# WBDR_02.net
KiCad netlist of a schematic drawn in EAGLE
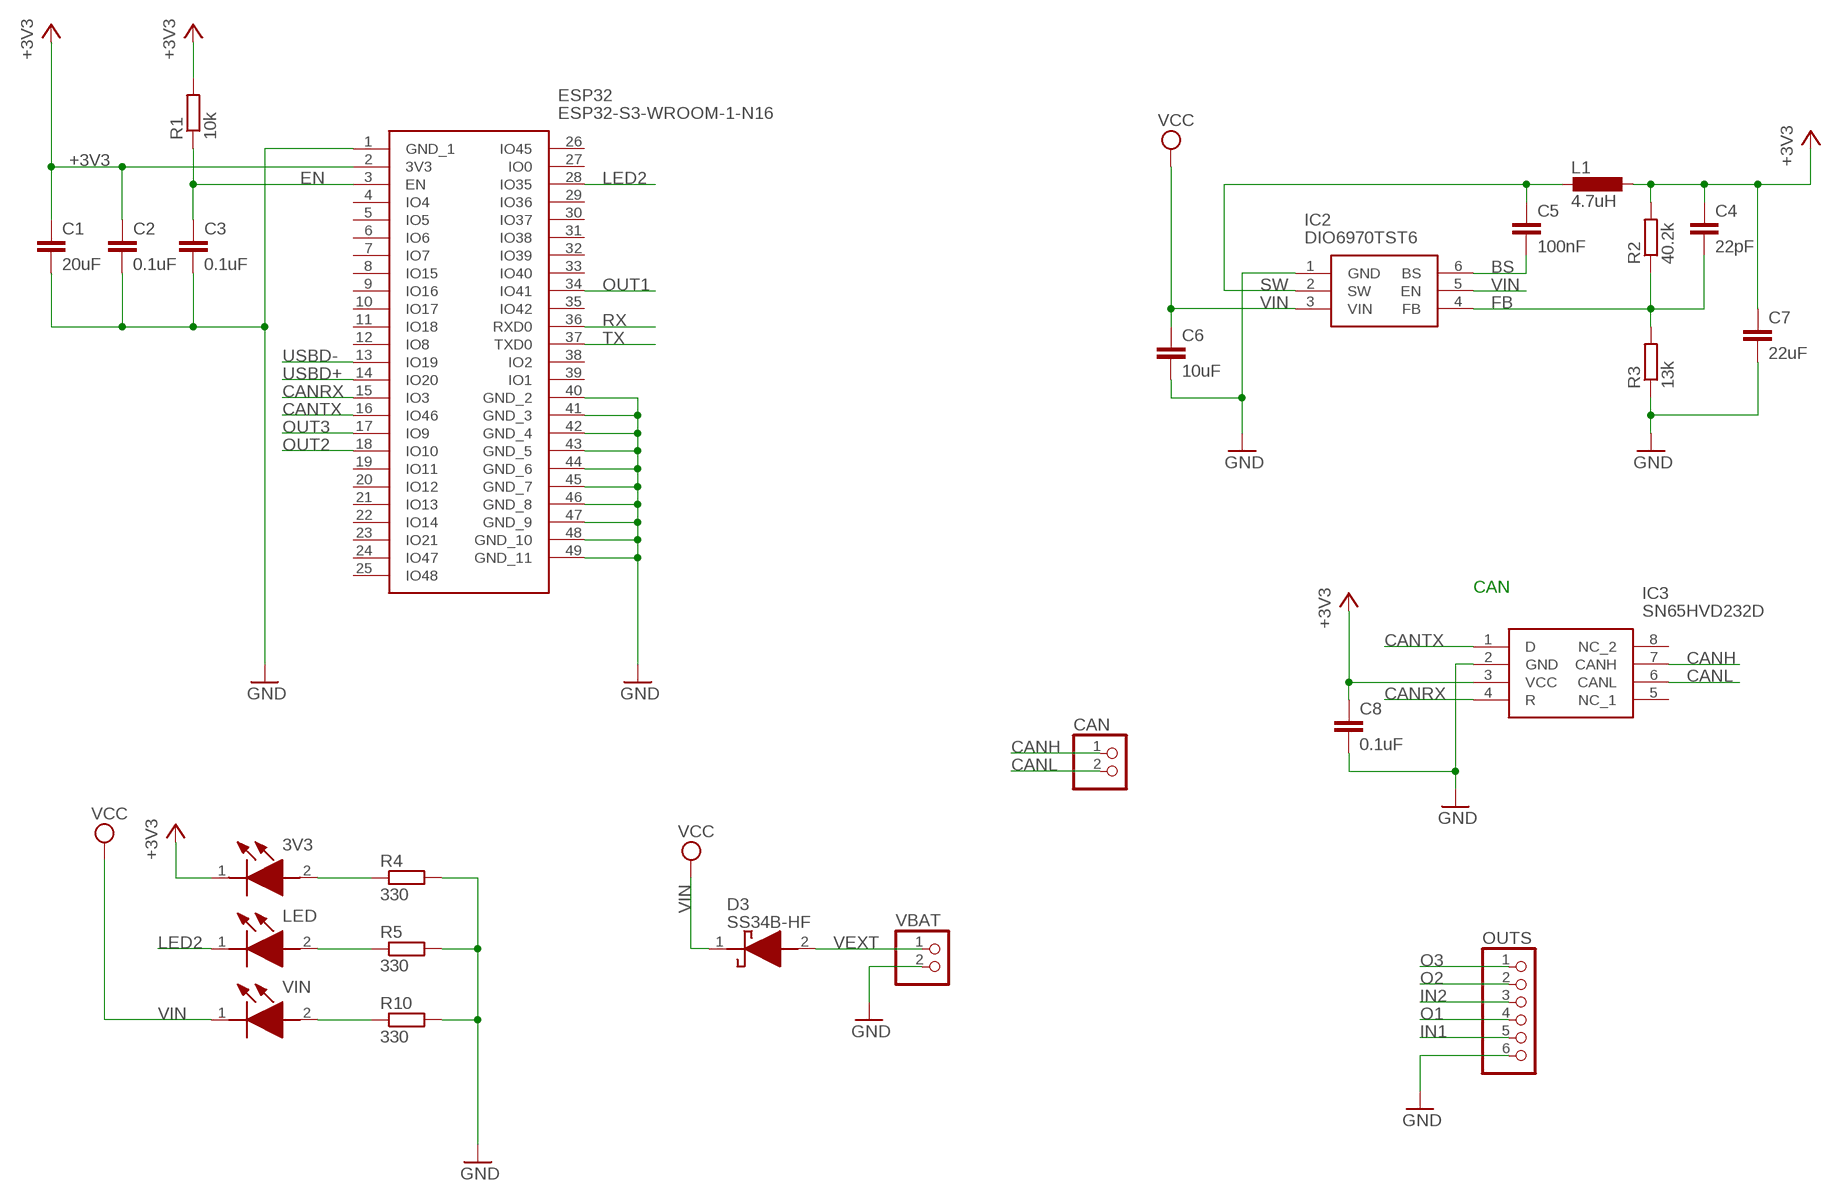
[diagram p0: schematic, sheet 1, part 1 of 2]
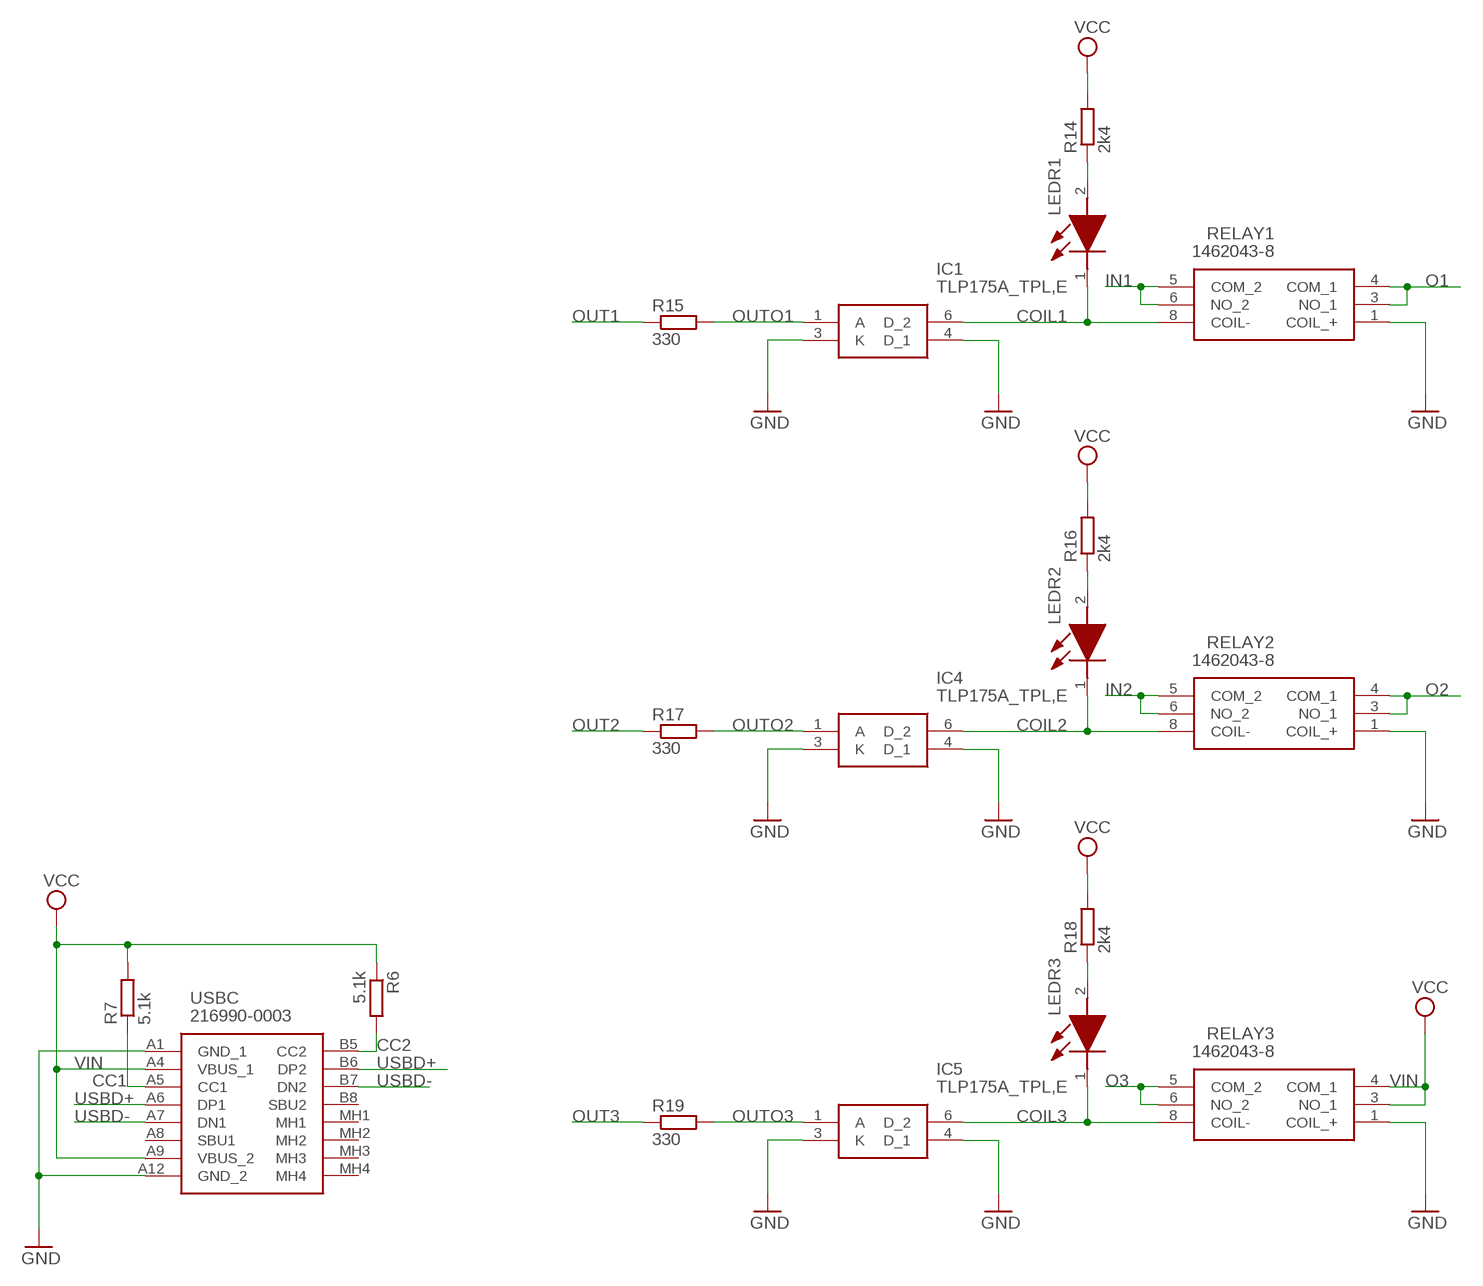
[diagram p1: schematic, sheet 1, part 2 of 2]

(export (version "E")
  (design (tool "Eeschema 10.0.6"))
  (components
    (comp (ref "3V3")
      (value "150060GS75000")
      (footprint "eagle-import:LEDC1608X80N")
      (fields (field (name "MOUSER_PART_NUMBER") "710-150060GS75000"))
      (libsource (lib "eagle-import") (part "150060GS75000"))
    )
    (comp (ref "C1")
      (value "20uF")
      (footprint "eagle-import:C0603")
      (libsource (lib "eagle-import") (part "C-EUC0603"))
    )
    (comp (ref "C2")
      (value "0.1uF")
      (footprint "eagle-import:C0603")
      (libsource (lib "eagle-import") (part "C-EUC0603"))
    )
    (comp (ref "C3")
      (value "0.1uF")
      (footprint "eagle-import:C0603")
      (libsource (lib "eagle-import") (part "C-EUC0603"))
    )
    (comp (ref "C4")
      (value "22pF")
      (footprint "eagle-import:C0603")
      (libsource (lib "eagle-import") (part "C-EUC0603"))
    )
    (comp (ref "C5")
      (value "100nF")
      (footprint "eagle-import:C0603")
      (libsource (lib "eagle-import") (part "C-EUC0603"))
    )
    (comp (ref "C6")
      (value "10uF")
      (footprint "eagle-import:C0603")
      (libsource (lib "eagle-import") (part "C-EUC0603"))
    )
    (comp (ref "C7")
      (value "22uF")
      (footprint "eagle-import:C0603")
      (libsource (lib "eagle-import") (part "C-EUC0603"))
    )
    (comp (ref "C8")
      (value "0.1uF")
      (footprint "eagle-import:C0603")
      (libsource (lib "eagle-import") (part "C-EUC0603"))
    )
    (comp (ref "CAN")
      (value "PINHD-1X2")
      (footprint "eagle-import:1X02")
      (libsource (lib "eagle-import") (part "PINHD-1X2"))
    )
    (comp (ref "D3")
      (value "SS34B-HF")
      (footprint "eagle-import:DIOM5336X320N")
      (fields (field (name "MOUSER_PART_NUMBER") "750-SS34B-HF"))
      (libsource (lib "eagle-import") (part "SS34B-HF"))
    )
    (comp (ref "ESP32")
      (value "ESP32-S3-WROOM-1-N16")
      (footprint "eagle-import:ESP32S3WROOM1N16")
      (fields (field (name "MOUSER_PART_NUMBER") "356-ESP32S3WROOM1N16"))
      (libsource (lib "eagle-import") (part "ESP32-S3-WROOM-1-N16"))
    )
    (comp (ref "IC1")
      (value "TLP175A_TPL,E")
      (footprint "eagle-import:TLP266J")
      (fields
        (field (name "MANUFACTURER_PART_NUMBER") "TLP175A(TPL,E")
        (field (name "MOUSER_PART_NUMBER") "757-TLP175A(TPLE")
      )
      (libsource (lib "eagle-import") (part "TLP175A_TPL,E"))
    )
    (comp (ref "IC2")
      (value "DIO6970TST6")
      (footprint "eagle-import:SOT95P280X90-6N")
      (fields (field (name "MOUSER_PART_NUMBER") "453-DIO6970ST6"))
      (libsource (lib "eagle-import") (part "DIO6970TST6"))
    )
    (comp (ref "IC3")
      (value "SN65HVD232D")
      (footprint "eagle-import:SOIC127P600X175-8N")
      (fields (field (name "MOUSER_PART_NUMBER") "595-SN65HVD232D"))
      (libsource (lib "eagle-import") (part "SN65HVD232D"))
    )
    (comp (ref "IC4")
      (value "TLP175A_TPL,E")
      (footprint "eagle-import:TLP266J")
      (fields
        (field (name "MANUFACTURER_PART_NUMBER") "TLP175A(TPL,E")
        (field (name "MOUSER_PART_NUMBER") "757-TLP175A(TPLE")
      )
      (libsource (lib "eagle-import") (part "TLP175A_TPL,E"))
    )
    (comp (ref "IC5")
      (value "TLP175A_TPL,E")
      (footprint "eagle-import:TLP266J")
      (fields
        (field (name "MANUFACTURER_PART_NUMBER") "TLP175A(TPL,E")
        (field (name "MOUSER_PART_NUMBER") "757-TLP175A(TPLE")
      )
      (libsource (lib "eagle-import") (part "TLP175A_TPL,E"))
    )
    (comp (ref "L1")
      (value "4.7uH")
      (footprint "eagle-import:L5650M")
      (libsource (lib "eagle-import") (part "L-EUL5650M"))
    )
    (comp (ref "LED")
      (value "150060GS75000")
      (footprint "eagle-import:LEDC1608X80N")
      (fields (field (name "MOUSER_PART_NUMBER") "710-150060GS75000"))
      (libsource (lib "eagle-import") (part "150060GS75000"))
    )
    (comp (ref "LEDR1")
      (value "150060GS75000")
      (footprint "eagle-import:LEDC1608X80N")
      (fields (field (name "MOUSER_PART_NUMBER") "710-150060GS75000"))
      (libsource (lib "eagle-import") (part "150060GS75000"))
    )
    (comp (ref "LEDR2")
      (value "150060GS75000")
      (footprint "eagle-import:LEDC1608X80N")
      (fields (field (name "MOUSER_PART_NUMBER") "710-150060GS75000"))
      (libsource (lib "eagle-import") (part "150060GS75000"))
    )
    (comp (ref "LEDR3")
      (value "150060GS75000")
      (footprint "eagle-import:LEDC1608X80N")
      (fields (field (name "MOUSER_PART_NUMBER") "710-150060GS75000"))
      (libsource (lib "eagle-import") (part "150060GS75000"))
    )
    (comp (ref "OUTS")
      (value "PINHD-1X6")
      (footprint "eagle-import:1X06")
      (libsource (lib "eagle-import") (part "PINHD-1X6"))
    )
    (comp (ref "R1")
      (value "10k")
      (footprint "eagle-import:R0603")
      (libsource (lib "eagle-import") (part "R-EU_R0603"))
    )
    (comp (ref "R2")
      (value "40.2k")
      (footprint "eagle-import:R0603")
      (libsource (lib "eagle-import") (part "R-EU_R0603"))
    )
    (comp (ref "R3")
      (value "13k")
      (footprint "eagle-import:R0603")
      (libsource (lib "eagle-import") (part "R-EU_R0603"))
    )
    (comp (ref "R4")
      (value "330")
      (footprint "eagle-import:R0603")
      (libsource (lib "eagle-import") (part "R-EU_R0603"))
    )
    (comp (ref "R5")
      (value "330")
      (footprint "eagle-import:R0603")
      (libsource (lib "eagle-import") (part "R-EU_R0603"))
    )
    (comp (ref "R6")
      (value "5.1k")
      (footprint "eagle-import:R0603")
      (libsource (lib "eagle-import") (part "R-EU_R0603"))
    )
    (comp (ref "R7")
      (value "5.1k")
      (footprint "eagle-import:R0603")
      (libsource (lib "eagle-import") (part "R-EU_R0603"))
    )
    (comp (ref "R10")
      (value "330")
      (footprint "eagle-import:R0603")
      (libsource (lib "eagle-import") (part "R-EU_R0603"))
    )
    (comp (ref "R14")
      (value "2k4")
      (footprint "eagle-import:R0603")
      (libsource (lib "eagle-import") (part "R-EU_R0603"))
    )
    (comp (ref "R15")
      (value "330")
      (footprint "eagle-import:R0603")
      (libsource (lib "eagle-import") (part "R-EU_R0603"))
    )
    (comp (ref "R16")
      (value "2k4")
      (footprint "eagle-import:R0603")
      (libsource (lib "eagle-import") (part "R-EU_R0603"))
    )
    (comp (ref "R17")
      (value "330")
      (footprint "eagle-import:R0603")
      (libsource (lib "eagle-import") (part "R-EU_R0603"))
    )
    (comp (ref "R18")
      (value "2k4")
      (footprint "eagle-import:R0603")
      (libsource (lib "eagle-import") (part "R-EU_R0603"))
    )
    (comp (ref "R19")
      (value "330")
      (footprint "eagle-import:R0603")
      (libsource (lib "eagle-import") (part "R-EU_R0603"))
    )
    (comp (ref "RELAY1")
      (value "1462043-8")
      (footprint "eagle-import:14620438")
      (fields (field (name "MOUSER_PART_NUMBER") "655-1462043-8"))
      (libsource (lib "eagle-import") (part "1462043-8"))
    )
    (comp (ref "RELAY2")
      (value "1462043-8")
      (footprint "eagle-import:14620438")
      (fields (field (name "MOUSER_PART_NUMBER") "655-1462043-8"))
      (libsource (lib "eagle-import") (part "1462043-8"))
    )
    (comp (ref "RELAY3")
      (value "1462043-8")
      (footprint "eagle-import:14620438")
      (fields (field (name "MOUSER_PART_NUMBER") "655-1462043-8"))
      (libsource (lib "eagle-import") (part "1462043-8"))
    )
    (comp (ref "USBC")
      (value "216990-0003")
      (footprint "eagle-import:2169900003")
      (fields (field (name "MOUSER_PART_NUMBER") "538-216990-0003"))
      (libsource (lib "eagle-import") (part "216990-0003"))
    )
    (comp (ref "VBAT")
      (value "PINHD-1X2")
      (footprint "eagle-import:1X02")
      (libsource (lib "eagle-import") (part "PINHD-1X2"))
    )
    (comp (ref "VIN")
      (value "150060GS75000")
      (footprint "eagle-import:LEDC1608X80N")
      (fields (field (name "MOUSER_PART_NUMBER") "710-150060GS75000"))
      (libsource (lib "eagle-import") (part "150060GS75000"))
    )
  )
  (nets
    (net (code "1") (name "+3V3") (class "Default")
      (node (ref "3V3") (pin "1") (pinfunction "K_1") (pintype "bidirectional"))
      (node (ref "C1") (pin "1") (pinfunction "1_1") (pintype "passive"))
      (node (ref "C2") (pin "1") (pinfunction "1_1") (pintype "passive"))
      (node (ref "C4") (pin "1") (pinfunction "1_1") (pintype "passive"))
      (node (ref "C7") (pin "1") (pinfunction "1_1") (pintype "passive"))
      (node (ref "C8") (pin "1") (pinfunction "1_1") (pintype "passive"))
      (node (ref "ESP32") (pin "2") (pinfunction "3V3_2") (pintype "bidirectional"))
      (node (ref "IC3") (pin "3") (pinfunction "VCC_3") (pintype "bidirectional"))
      (node (ref "L1") (pin "1") (pinfunction "1_1") (pintype "passive"))
      (node (ref "R1") (pin "2") (pinfunction "2_2") (pintype "passive"))
      (node (ref "R2") (pin "2") (pinfunction "2_2") (pintype "passive"))
    )
    (net (code "2") (name "/BS") (class "Default")
      (node (ref "C5") (pin "2") (pinfunction "2_2") (pintype "passive"))
      (node (ref "IC2") (pin "6") (pinfunction "BS_6") (pintype "bidirectional"))
    )
    (net (code "3") (name "/CANH") (class "Default")
      (node (ref "CAN") (pin "1") (pinfunction "1_1") (pintype "passive"))
      (node (ref "IC3") (pin "7") (pinfunction "CANH_7") (pintype "bidirectional"))
    )
    (net (code "4") (name "/CANL") (class "Default")
      (node (ref "CAN") (pin "2") (pinfunction "2_2") (pintype "passive"))
      (node (ref "IC3") (pin "6") (pinfunction "CANL_6") (pintype "bidirectional"))
    )
    (net (code "5") (name "/CANRX") (class "Default")
      (node (ref "ESP32") (pin "15") (pinfunction "IO3_15") (pintype "bidirectional"))
      (node (ref "IC3") (pin "4") (pinfunction "R_4") (pintype "bidirectional"))
    )
    (net (code "6") (name "/CANTX") (class "Default")
      (node (ref "ESP32") (pin "16") (pinfunction "IO46_16") (pintype "bidirectional"))
      (node (ref "IC3") (pin "1") (pinfunction "D_1") (pintype "bidirectional"))
    )
    (net (code "7") (name "/CC1") (class "Default")
      (node (ref "R7") (pin "1") (pinfunction "1_1") (pintype "passive"))
      (node (ref "USBC") (pin "A5") (pinfunction "CC1_A5") (pintype "bidirectional"))
    )
    (net (code "8") (name "/CC2") (class "Default")
      (node (ref "R6") (pin "2") (pinfunction "2_2") (pintype "passive"))
      (node (ref "USBC") (pin "B5") (pinfunction "CC2_B5") (pintype "bidirectional"))
    )
    (net (code "9") (name "/COIL1") (class "Default")
      (node (ref "IC1") (pin "6") (pinfunction "D_2_6") (pintype "bidirectional"))
      (node (ref "LEDR1") (pin "1") (pinfunction "K_1") (pintype "bidirectional"))
      (node (ref "RELAY1") (pin "8") (pinfunction "COIL-_8") (pintype "bidirectional"))
    )
    (net (code "10") (name "/COIL2") (class "Default")
      (node (ref "IC4") (pin "6") (pinfunction "D_2_6") (pintype "bidirectional"))
      (node (ref "LEDR2") (pin "1") (pinfunction "K_1") (pintype "bidirectional"))
      (node (ref "RELAY2") (pin "8") (pinfunction "COIL-_8") (pintype "bidirectional"))
    )
    (net (code "11") (name "/COIL3") (class "Default")
      (node (ref "IC5") (pin "6") (pinfunction "D_2_6") (pintype "bidirectional"))
      (node (ref "LEDR3") (pin "1") (pinfunction "K_1") (pintype "bidirectional"))
      (node (ref "RELAY3") (pin "8") (pinfunction "COIL-_8") (pintype "bidirectional"))
    )
    (net (code "12") (name "/EN") (class "Default")
      (node (ref "C3") (pin "1") (pinfunction "1_1") (pintype "passive"))
      (node (ref "ESP32") (pin "3") (pinfunction "EN_3") (pintype "bidirectional"))
      (node (ref "R1") (pin "1") (pinfunction "1_1") (pintype "passive"))
    )
    (net (code "13") (name "/FB") (class "Default")
      (node (ref "C4") (pin "2") (pinfunction "2_2") (pintype "passive"))
      (node (ref "IC2") (pin "4") (pinfunction "FB_4") (pintype "bidirectional"))
      (node (ref "R2") (pin "1") (pinfunction "1_1") (pintype "passive"))
      (node (ref "R3") (pin "2") (pinfunction "2_2") (pintype "passive"))
    )
    (net (code "14") (name "/IN1") (class "Default")
      (node (ref "OUTS") (pin "5") (pinfunction "5_5") (pintype "passive"))
      (node (ref "RELAY1") (pin "5") (pinfunction "COM_2_5") (pintype "bidirectional"))
      (node (ref "RELAY1") (pin "6") (pinfunction "NO_2_6") (pintype "bidirectional"))
    )
    (net (code "15") (name "/IN2") (class "Default")
      (node (ref "OUTS") (pin "3") (pinfunction "3_3") (pintype "passive"))
      (node (ref "RELAY2") (pin "5") (pinfunction "COM_2_5") (pintype "bidirectional"))
      (node (ref "RELAY2") (pin "6") (pinfunction "NO_2_6") (pintype "bidirectional"))
    )
    (net (code "16") (name "/LED2") (class "Default")
      (node (ref "ESP32") (pin "28") (pinfunction "IO35_28") (pintype "bidirectional"))
      (node (ref "LED") (pin "1") (pinfunction "K_1") (pintype "bidirectional"))
    )
    (net (code "17") (name "/O1") (class "Default")
      (node (ref "OUTS") (pin "4") (pinfunction "4_4") (pintype "passive"))
      (node (ref "RELAY1") (pin "3") (pinfunction "NO_1_3") (pintype "bidirectional"))
      (node (ref "RELAY1") (pin "4") (pinfunction "COM_1_4") (pintype "bidirectional"))
    )
    (net (code "18") (name "/O2") (class "Default")
      (node (ref "OUTS") (pin "2") (pinfunction "2_2") (pintype "passive"))
      (node (ref "RELAY2") (pin "3") (pinfunction "NO_1_3") (pintype "bidirectional"))
      (node (ref "RELAY2") (pin "4") (pinfunction "COM_1_4") (pintype "bidirectional"))
    )
    (net (code "19") (name "/O3") (class "Default")
      (node (ref "OUTS") (pin "1") (pinfunction "1_1") (pintype "passive"))
      (node (ref "RELAY3") (pin "5") (pinfunction "COM_2_5") (pintype "bidirectional"))
      (node (ref "RELAY3") (pin "6") (pinfunction "NO_2_6") (pintype "bidirectional"))
    )
    (net (code "20") (name "/OUT1") (class "Default")
      (node (ref "ESP32") (pin "34") (pinfunction "IO41_34") (pintype "bidirectional"))
      (node (ref "R15") (pin "1") (pinfunction "1_1") (pintype "passive"))
    )
    (net (code "21") (name "/OUT2") (class "Default")
      (node (ref "ESP32") (pin "18") (pinfunction "IO10_18") (pintype "bidirectional"))
      (node (ref "R17") (pin "1") (pinfunction "1_1") (pintype "passive"))
    )
    (net (code "22") (name "/OUT3") (class "Default")
      (node (ref "ESP32") (pin "17") (pinfunction "IO9_17") (pintype "bidirectional"))
      (node (ref "R19") (pin "1") (pinfunction "1_1") (pintype "passive"))
    )
    (net (code "23") (name "/OUTO1") (class "Default")
      (node (ref "IC1") (pin "1") (pinfunction "A_1") (pintype "bidirectional"))
      (node (ref "R15") (pin "2") (pinfunction "2_2") (pintype "passive"))
    )
    (net (code "24") (name "/OUTO2") (class "Default")
      (node (ref "IC4") (pin "1") (pinfunction "A_1") (pintype "bidirectional"))
      (node (ref "R17") (pin "2") (pinfunction "2_2") (pintype "passive"))
    )
    (net (code "25") (name "/OUTO3") (class "Default")
      (node (ref "IC5") (pin "1") (pinfunction "A_1") (pintype "bidirectional"))
      (node (ref "R19") (pin "2") (pinfunction "2_2") (pintype "passive"))
    )
    (net (code "26") (name "/RX") (class "Default")
      (node (ref "ESP32") (pin "36") (pinfunction "RXD0_36") (pintype "bidirectional"))
    )
    (net (code "27") (name "/SW") (class "Default")
      (node (ref "C5") (pin "1") (pinfunction "1_1") (pintype "passive"))
      (node (ref "IC2") (pin "2") (pinfunction "SW_2") (pintype "bidirectional"))
      (node (ref "L1") (pin "2") (pinfunction "2_2") (pintype "passive"))
    )
    (net (code "28") (name "/TX") (class "Default")
      (node (ref "ESP32") (pin "37") (pinfunction "TXD0_37") (pintype "bidirectional"))
    )
    (net (code "29") (name "/USBD+") (class "Default")
      (node (ref "ESP32") (pin "14") (pinfunction "IO20_14") (pintype "bidirectional"))
      (node (ref "USBC") (pin "A6") (pinfunction "DP1_A6") (pintype "bidirectional"))
      (node (ref "USBC") (pin "B6") (pinfunction "DP2_B6") (pintype "bidirectional"))
    )
    (net (code "30") (name "/USBD-") (class "Default")
      (node (ref "ESP32") (pin "13") (pinfunction "IO19_13") (pintype "bidirectional"))
      (node (ref "USBC") (pin "A7") (pinfunction "DN1_A7") (pintype "bidirectional"))
      (node (ref "USBC") (pin "B7") (pinfunction "DN2_B7") (pintype "bidirectional"))
    )
    (net (code "31") (name "/VEXT") (class "Default")
      (node (ref "D3") (pin "2") (pinfunction "A_2") (pintype "bidirectional"))
      (node (ref "VBAT") (pin "1") (pinfunction "1_1") (pintype "passive"))
    )
    (net (code "32") (name "GND") (class "Default")
      (node (ref "C1") (pin "2") (pinfunction "2_2") (pintype "passive"))
      (node (ref "C2") (pin "2") (pinfunction "2_2") (pintype "passive"))
      (node (ref "C3") (pin "2") (pinfunction "2_2") (pintype "passive"))
      (node (ref "C6") (pin "2") (pinfunction "2_2") (pintype "passive"))
      (node (ref "C7") (pin "2") (pinfunction "2_2") (pintype "passive"))
      (node (ref "C8") (pin "2") (pinfunction "2_2") (pintype "passive"))
      (node (ref "ESP32") (pin "1") (pinfunction "GND_1_1") (pintype "bidirectional"))
      (node (ref "ESP32") (pin "40") (pinfunction "GND_2_40") (pintype "bidirectional"))
      (node (ref "ESP32") (pin "41") (pinfunction "GND_3_41") (pintype "bidirectional"))
      (node (ref "ESP32") (pin "42") (pinfunction "GND_4_42") (pintype "bidirectional"))
      (node (ref "ESP32") (pin "43") (pinfunction "GND_5_43") (pintype "bidirectional"))
      (node (ref "ESP32") (pin "44") (pinfunction "GND_6_44") (pintype "bidirectional"))
      (node (ref "ESP32") (pin "45") (pinfunction "GND_7_45") (pintype "bidirectional"))
      (node (ref "ESP32") (pin "46") (pinfunction "GND_8_46") (pintype "bidirectional"))
      (node (ref "ESP32") (pin "47") (pinfunction "GND_9_47") (pintype "bidirectional"))
      (node (ref "ESP32") (pin "48") (pinfunction "GND_10_48") (pintype "bidirectional"))
      (node (ref "ESP32") (pin "49") (pinfunction "GND_11_49") (pintype "bidirectional"))
      (node (ref "IC1") (pin "3") (pinfunction "K_3") (pintype "bidirectional"))
      (node (ref "IC1") (pin "4") (pinfunction "D_1_4") (pintype "bidirectional"))
      (node (ref "IC2") (pin "1") (pinfunction "GND_1") (pintype "bidirectional"))
      (node (ref "IC3") (pin "2") (pinfunction "GND_2") (pintype "bidirectional"))
      (node (ref "IC4") (pin "3") (pinfunction "K_3") (pintype "bidirectional"))
      (node (ref "IC4") (pin "4") (pinfunction "D_1_4") (pintype "bidirectional"))
      (node (ref "IC5") (pin "3") (pinfunction "K_3") (pintype "bidirectional"))
      (node (ref "IC5") (pin "4") (pinfunction "D_1_4") (pintype "bidirectional"))
      (node (ref "OUTS") (pin "6") (pinfunction "6_6") (pintype "passive"))
      (node (ref "R10") (pin "2") (pinfunction "2_2") (pintype "passive"))
      (node (ref "R3") (pin "1") (pinfunction "1_1") (pintype "passive"))
      (node (ref "R4") (pin "2") (pinfunction "2_2") (pintype "passive"))
      (node (ref "R5") (pin "2") (pinfunction "2_2") (pintype "passive"))
      (node (ref "RELAY1") (pin "1") (pinfunction "COIL_+_1") (pintype "bidirectional"))
      (node (ref "RELAY2") (pin "1") (pinfunction "COIL_+_1") (pintype "bidirectional"))
      (node (ref "RELAY3") (pin "1") (pinfunction "COIL_+_1") (pintype "bidirectional"))
      (node (ref "USBC") (pin "A1") (pinfunction "GND_1_A1") (pintype "bidirectional"))
      (node (ref "USBC") (pin "A12") (pinfunction "GND_2_A12") (pintype "bidirectional"))
      (node (ref "VBAT") (pin "2") (pinfunction "2_2") (pintype "passive"))
    )
    (net (code "33") (name "Net-(3V3-A)") (class "Default")
      (node (ref "3V3") (pin "2") (pinfunction "A_2") (pintype "bidirectional"))
      (node (ref "R4") (pin "1") (pinfunction "1_1") (pintype "passive"))
    )
    (net (code "34") (name "Net-(LED-A)") (class "Default")
      (node (ref "LED") (pin "2") (pinfunction "A_2") (pintype "bidirectional"))
      (node (ref "R5") (pin "1") (pinfunction "1_1") (pintype "passive"))
    )
    (net (code "35") (name "Net-(LEDR1-A)") (class "Default")
      (node (ref "LEDR1") (pin "2") (pinfunction "A_2") (pintype "bidirectional"))
      (node (ref "R14") (pin "1") (pinfunction "1_1") (pintype "passive"))
    )
    (net (code "36") (name "Net-(LEDR2-A)") (class "Default")
      (node (ref "LEDR2") (pin "2") (pinfunction "A_2") (pintype "bidirectional"))
      (node (ref "R16") (pin "1") (pinfunction "1_1") (pintype "passive"))
    )
    (net (code "37") (name "Net-(LEDR3-A)") (class "Default")
      (node (ref "LEDR3") (pin "2") (pinfunction "A_2") (pintype "bidirectional"))
      (node (ref "R18") (pin "1") (pinfunction "1_1") (pintype "passive"))
    )
    (net (code "38") (name "Net-(VIN-A)") (class "Default")
      (node (ref "R10") (pin "1") (pinfunction "1_1") (pintype "passive"))
      (node (ref "VIN") (pin "2") (pinfunction "A_2") (pintype "bidirectional"))
    )
    (net (code "39") (name "VCC") (class "Default")
      (node (ref "C6") (pin "1") (pinfunction "1_1") (pintype "passive"))
      (node (ref "D3") (pin "1") (pinfunction "K_1") (pintype "bidirectional"))
      (node (ref "IC2") (pin "3") (pinfunction "VIN_3") (pintype "bidirectional"))
      (node (ref "IC2") (pin "5") (pinfunction "EN_5") (pintype "bidirectional"))
      (node (ref "R14") (pin "2") (pinfunction "2_2") (pintype "passive"))
      (node (ref "R16") (pin "2") (pinfunction "2_2") (pintype "passive"))
      (node (ref "R18") (pin "2") (pinfunction "2_2") (pintype "passive"))
      (node (ref "R6") (pin "1") (pinfunction "1_1") (pintype "passive"))
      (node (ref "R7") (pin "2") (pinfunction "2_2") (pintype "passive"))
      (node (ref "RELAY3") (pin "3") (pinfunction "NO_1_3") (pintype "bidirectional"))
      (node (ref "RELAY3") (pin "4") (pinfunction "COM_1_4") (pintype "bidirectional"))
      (node (ref "USBC") (pin "A4") (pinfunction "VBUS_1_A4") (pintype "bidirectional"))
      (node (ref "USBC") (pin "A9") (pinfunction "VBUS_2_A9") (pintype "bidirectional"))
      (node (ref "VIN") (pin "1") (pinfunction "K_1") (pintype "bidirectional"))
    )
    (net (code "40") (name "unconnected-(ESP32-IO0-Pad27)") (class "Default")
      (node (ref "ESP32") (pin "27") (pinfunction "IO0_27") (pintype "bidirectional"))
    )
    (net (code "41") (name "unconnected-(ESP32-IO1-Pad39)") (class "Default")
      (node (ref "ESP32") (pin "39") (pinfunction "IO1_39") (pintype "bidirectional"))
    )
    (net (code "42") (name "unconnected-(ESP32-IO2-Pad38)") (class "Default")
      (node (ref "ESP32") (pin "38") (pinfunction "IO2_38") (pintype "bidirectional"))
    )
    (net (code "43") (name "unconnected-(ESP32-IO4-Pad4)") (class "Default")
      (node (ref "ESP32") (pin "4") (pinfunction "IO4_4") (pintype "bidirectional"))
    )
    (net (code "44") (name "unconnected-(ESP32-IO5-Pad5)") (class "Default")
      (node (ref "ESP32") (pin "5") (pinfunction "IO5_5") (pintype "bidirectional"))
    )
    (net (code "45") (name "unconnected-(ESP32-IO6-Pad6)") (class "Default")
      (node (ref "ESP32") (pin "6") (pinfunction "IO6_6") (pintype "bidirectional"))
    )
    (net (code "46") (name "unconnected-(ESP32-IO7-Pad7)") (class "Default")
      (node (ref "ESP32") (pin "7") (pinfunction "IO7_7") (pintype "bidirectional"))
    )
    (net (code "47") (name "unconnected-(ESP32-IO8-Pad12)") (class "Default")
      (node (ref "ESP32") (pin "12") (pinfunction "IO8_12") (pintype "bidirectional"))
    )
    (net (code "48") (name "unconnected-(ESP32-IO11-Pad19)") (class "Default")
      (node (ref "ESP32") (pin "19") (pinfunction "IO11_19") (pintype "bidirectional"))
    )
    (net (code "49") (name "unconnected-(ESP32-IO12-Pad20)") (class "Default")
      (node (ref "ESP32") (pin "20") (pinfunction "IO12_20") (pintype "bidirectional"))
    )
    (net (code "50") (name "unconnected-(ESP32-IO13-Pad21)") (class "Default")
      (node (ref "ESP32") (pin "21") (pinfunction "IO13_21") (pintype "bidirectional"))
    )
    (net (code "51") (name "unconnected-(ESP32-IO14-Pad22)") (class "Default")
      (node (ref "ESP32") (pin "22") (pinfunction "IO14_22") (pintype "bidirectional"))
    )
    (net (code "52") (name "unconnected-(ESP32-IO15-Pad8)") (class "Default")
      (node (ref "ESP32") (pin "8") (pinfunction "IO15_8") (pintype "bidirectional"))
    )
    (net (code "53") (name "unconnected-(ESP32-IO16-Pad9)") (class "Default")
      (node (ref "ESP32") (pin "9") (pinfunction "IO16_9") (pintype "bidirectional"))
    )
    (net (code "54") (name "unconnected-(ESP32-IO17-Pad10)") (class "Default")
      (node (ref "ESP32") (pin "10") (pinfunction "IO17_10") (pintype "bidirectional"))
    )
    (net (code "55") (name "unconnected-(ESP32-IO18-Pad11)") (class "Default")
      (node (ref "ESP32") (pin "11") (pinfunction "IO18_11") (pintype "bidirectional"))
    )
    (net (code "56") (name "unconnected-(ESP32-IO21-Pad23)") (class "Default")
      (node (ref "ESP32") (pin "23") (pinfunction "IO21_23") (pintype "bidirectional"))
    )
    (net (code "57") (name "unconnected-(ESP32-IO36-Pad29)") (class "Default")
      (node (ref "ESP32") (pin "29") (pinfunction "IO36_29") (pintype "bidirectional"))
    )
    (net (code "58") (name "unconnected-(ESP32-IO37-Pad30)") (class "Default")
      (node (ref "ESP32") (pin "30") (pinfunction "IO37_30") (pintype "bidirectional"))
    )
    (net (code "59") (name "unconnected-(ESP32-IO38-Pad31)") (class "Default")
      (node (ref "ESP32") (pin "31") (pinfunction "IO38_31") (pintype "bidirectional"))
    )
    (net (code "60") (name "unconnected-(ESP32-IO39-Pad32)") (class "Default")
      (node (ref "ESP32") (pin "32") (pinfunction "IO39_32") (pintype "bidirectional"))
    )
    (net (code "61") (name "unconnected-(ESP32-IO40-Pad33)") (class "Default")
      (node (ref "ESP32") (pin "33") (pinfunction "IO40_33") (pintype "bidirectional"))
    )
    (net (code "62") (name "unconnected-(ESP32-IO42-Pad35)") (class "Default")
      (node (ref "ESP32") (pin "35") (pinfunction "IO42_35") (pintype "bidirectional"))
    )
    (net (code "63") (name "unconnected-(ESP32-IO45-Pad26)") (class "Default")
      (node (ref "ESP32") (pin "26") (pinfunction "IO45_26") (pintype "bidirectional"))
    )
    (net (code "64") (name "unconnected-(ESP32-IO47-Pad24)") (class "Default")
      (node (ref "ESP32") (pin "24") (pinfunction "IO47_24") (pintype "bidirectional"))
    )
    (net (code "65") (name "unconnected-(ESP32-IO48-Pad25)") (class "Default")
      (node (ref "ESP32") (pin "25") (pinfunction "IO48_25") (pintype "bidirectional"))
    )
    (net (code "66") (name "unconnected-(IC3-NC_1-Pad5)") (class "Default")
      (node (ref "IC3") (pin "5") (pinfunction "NC_1_5") (pintype "bidirectional"))
    )
    (net (code "67") (name "unconnected-(IC3-NC_2-Pad8)") (class "Default")
      (node (ref "IC3") (pin "8") (pinfunction "NC_2_8") (pintype "bidirectional"))
    )
    (net (code "68") (name "unconnected-(USBC-PadMH1)") (class "Default")
      (node (ref "USBC") (pin "MH1") (pinfunction "MH1_MH1") (pintype "bidirectional"))
    )
    (net (code "69") (name "unconnected-(USBC-PadMH2)") (class "Default")
      (node (ref "USBC") (pin "MH2") (pinfunction "MH2_MH2") (pintype "bidirectional"))
    )
    (net (code "70") (name "unconnected-(USBC-PadMH3)") (class "Default")
      (node (ref "USBC") (pin "MH3") (pinfunction "MH3_MH3") (pintype "bidirectional"))
    )
    (net (code "71") (name "unconnected-(USBC-PadMH4)") (class "Default")
      (node (ref "USBC") (pin "MH4") (pinfunction "MH4_MH4") (pintype "bidirectional"))
    )
    (net (code "72") (name "unconnected-(USBC-SBU1-PadA8)") (class "Default")
      (node (ref "USBC") (pin "A8") (pinfunction "SBU1_A8") (pintype "bidirectional"))
    )
    (net (code "73") (name "unconnected-(USBC-SBU2-PadB8)") (class "Default")
      (node (ref "USBC") (pin "B8") (pinfunction "SBU2_B8") (pintype "bidirectional"))
    )
  )
)
